# M_2_Circuit.net
KiCad netlist of a schematic drawn in Altium Designer
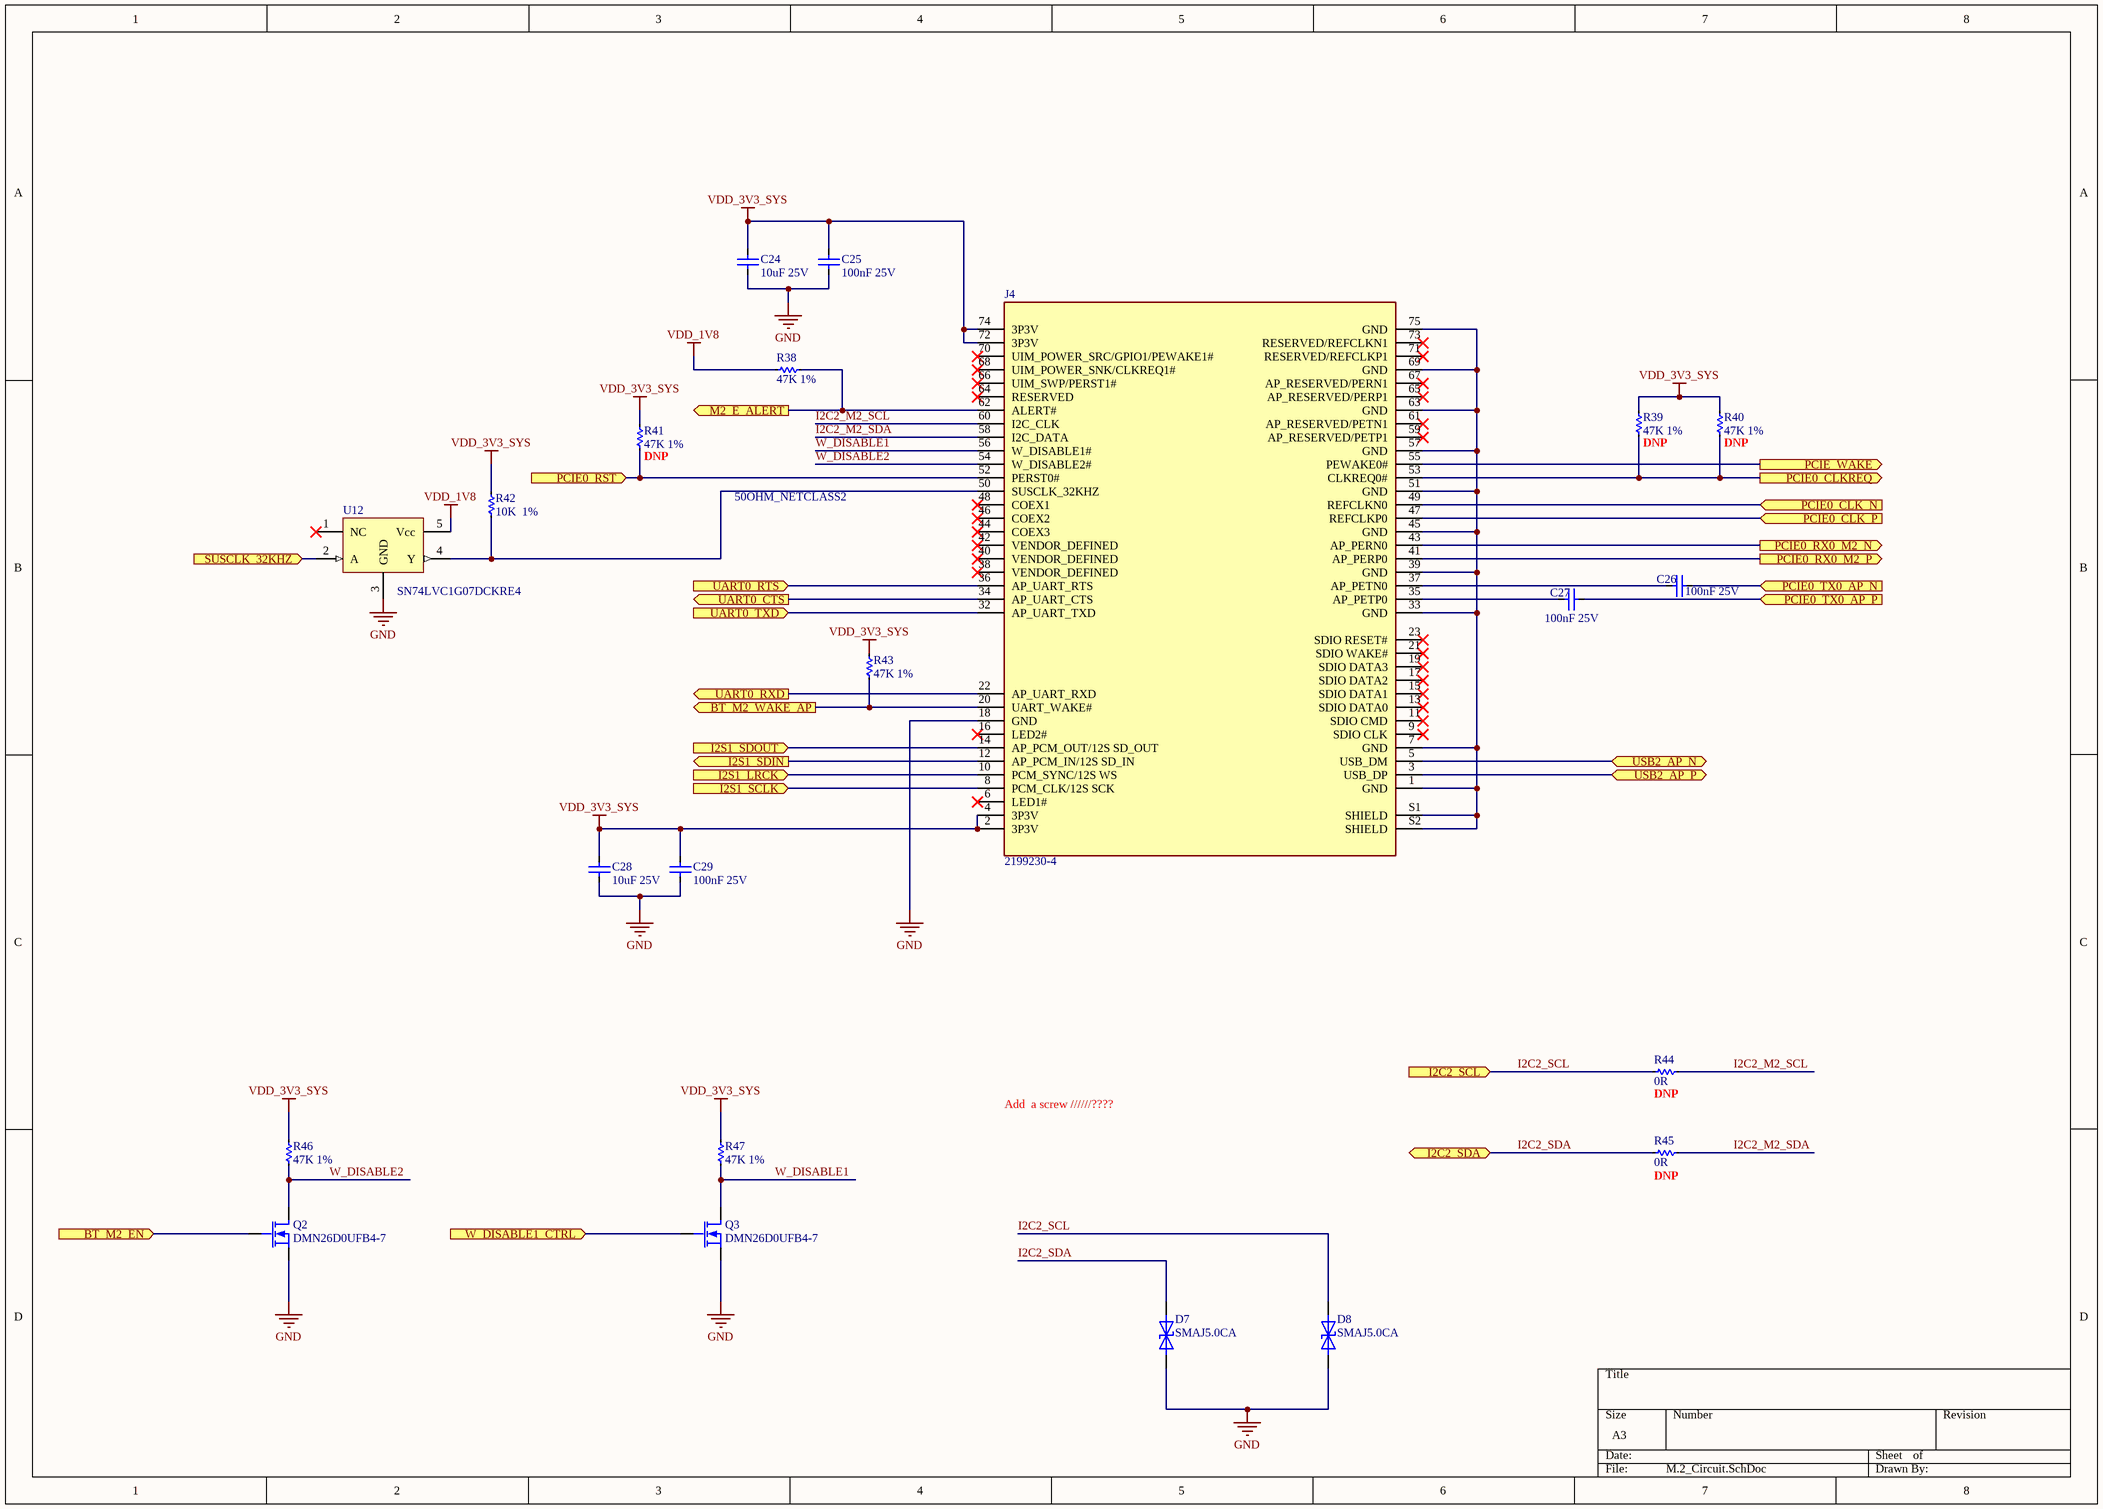
[diagram p0: M.2_Circuit.SchDoc]

(export (version "E")
  (design (tool "Eeschema 10.0.6"))
  (components
    (comp (ref "C24")
      (value "10uF 25V")
      (footprint "C0805")
      (description "Ceramic capacitor SMD-0805 10000nF (10uF) /25V X5R# M +-20% Samsung , RoHS/3000pcs/")
      (fields
        (field (name "MANUFACTURER") "Samsung")
        (field (name "MANUFACTURER PART NUMBER") "CL21A106KAYNNNG")
      )
      (libsource (lib "GM_Altium_Library") (part "CL21A106KAYNNNG"))
    )
    (comp (ref "C25")
      (value "100nF 25V")
      (footprint "C0402")
      (description "CAP CER 0.1UF 25V X5R 0402 / High Value Multilayer Ceramic Capacitors (High dielectric type)")
      (fields
        (field (name "MANUFACTURER") "Taiyo Yuden")
        (field (name "MANUFACTURER PART NUMBER") "TMK105BJ104KV-F")
      )
      (libsource (lib "GM_Altium_Library") (part "TMK105BJ104KV-F"))
    )
    (comp (ref "C26")
      (value "100nF 25V")
      (footprint "C0402")
      (description "CAP CER 0.1UF 25V X5R 0402 / High Value Multilayer Ceramic Capacitors (High dielectric type)")
      (fields
        (field (name "MANUFACTURER") "Taiyo Yuden")
        (field (name "MANUFACTURER PART NUMBER") "TMK105BJ104KV-F")
      )
      (libsource (lib "GM_Altium_Library") (part "TMK105BJ104KV-F"))
    )
    (comp (ref "C27")
      (value "100nF 25V")
      (footprint "C0402")
      (description "CAP CER 0.1UF 25V X5R 0402 / High Value Multilayer Ceramic Capacitors (High dielectric type)")
      (fields
        (field (name "MANUFACTURER") "Taiyo Yuden")
        (field (name "MANUFACTURER PART NUMBER") "TMK105BJ104KV-F")
      )
      (libsource (lib "GM_Altium_Library") (part "TMK105BJ104KV-F"))
    )
    (comp (ref "C28")
      (value "10uF 25V")
      (footprint "C0805")
      (description "Ceramic capacitor SMD-0805 10000nF (10uF) /25V X5R# M +-20% Samsung , RoHS/3000pcs/")
      (fields
        (field (name "MANUFACTURER") "Samsung")
        (field (name "MANUFACTURER PART NUMBER") "CL21A106KAYNNNG")
      )
      (libsource (lib "GM_Altium_Library") (part "CL21A106KAYNNNG"))
    )
    (comp (ref "C29")
      (value "100nF 25V")
      (footprint "C0402")
      (description "CAP CER 0.1UF 25V X5R 0402 / High Value Multilayer Ceramic Capacitors (High dielectric type)")
      (fields
        (field (name "MANUFACTURER") "Taiyo Yuden")
        (field (name "MANUFACTURER PART NUMBER") "TMK105BJ104KV-F")
      )
      (libsource (lib "GM_Altium_Library") (part "TMK105BJ104KV-F"))
    )
    (comp (ref "D7")
      (value "SMAJ5.0CA")
      (footprint "DO-214AC")
      (fields (field (name "MANUFACTURER") "Littelfuse"))
      (libsource (lib "GM_Altium_Library") (part "SMAJ5.0CA"))
    )
    (comp (ref "D8")
      (value "SMAJ5.0CA")
      (footprint "DO-214AC")
      (fields (field (name "MANUFACTURER") "Littelfuse"))
      (libsource (lib "GM_Altium_Library") (part "SMAJ5.0CA"))
    )
    (comp (ref "J4")
      (value "2199230-4")
      (footprint "2199230-4")
      (description "Conn Card Edge SKT 67 POS 0.5mm Solder RA SMD T/R")
      (fields (field (name "MANUFACTURER") "TE Connectivity"))
      (libsource (lib "GM_Connector") (part "2199230-4"))
    )
    (comp (ref "Q2")
      (value "DMN26D0UFB4-7")
      (footprint "DFN1006-3")
      (description "Single N-Channel 20 V 350 mW Silicon Surface Mount Mosfet - DFN-3")
      (fields (field (name "MANUFACTURER") "Diodes"))
      (libsource (lib "GM_Altium_Library") (part "DMN26D0UFB4-7"))
    )
    (comp (ref "Q3")
      (value "DMN26D0UFB4-7")
      (footprint "DFN1006-3")
      (description "Single N-Channel 20 V 350 mW Silicon Surface Mount Mosfet - DFN-3")
      (fields (field (name "MANUFACTURER") "Diodes"))
      (libsource (lib "GM_Altium_Library") (part "DMN26D0UFB4-7"))
    )
    (comp (ref "R38")
      (value "47K 1%")
      (footprint "R0402")
      (description "Res General Purpose Thick Film 0402 47K Ohm 1% 1/16W ±100ppm/°C Molded SMD Paper T/R")
      (fields
        (field (name "MANUFACTURER") "Yageo")
        (field (name "MANUFACTURER PART NUMBER") "RC0402FR-0747KL")
      )
      (libsource (lib "GM_Altium_Library") (part "RC0402FR-0747KL"))
    )
    (comp (ref "R39")
      (value "47K 1%")
      (footprint "R0402")
      (description "Res General Purpose Thick Film 0402 47K Ohm 1% 1/16W ±100ppm/°C Molded SMD Paper T/R")
      (fields
        (field (name "MANUFACTURER") "Yageo")
        (field (name "MANUFACTURER PART NUMBER") "RC0402FR-0747KL")
      )
      (libsource (lib "GM_Altium_Library") (part "RC0402FR-0747KL"))
    )
    (comp (ref "R40")
      (value "47K 1%")
      (footprint "R0402")
      (description "Res General Purpose Thick Film 0402 47K Ohm 1% 1/16W ±100ppm/°C Molded SMD Paper T/R")
      (fields
        (field (name "MANUFACTURER") "Yageo")
        (field (name "MANUFACTURER PART NUMBER") "RC0402FR-0747KL")
      )
      (libsource (lib "GM_Altium_Library") (part "RC0402FR-0747KL"))
    )
    (comp (ref "R41")
      (value "47K 1%")
      (footprint "R0402")
      (description "Res General Purpose Thick Film 0402 47K Ohm 1% 1/16W ±100ppm/°C Molded SMD Paper T/R")
      (fields
        (field (name "MANUFACTURER") "Yageo")
        (field (name "MANUFACTURER PART NUMBER") "RC0402FR-0747KL")
      )
      (libsource (lib "GM_Altium_Library") (part "RC0402FR-0747KL"))
    )
    (comp (ref "R42")
      (value "10K  1%")
      (footprint "R0402")
      (description "Res General Purpose Thick Film 0402 10K Ohm 1% 1/16W ±100ppm/°C Molded SMD Paper T/R")
      (fields
        (field (name "MANUFACTURER") "Yageo")
        (field (name "MANUFACTURER PART NUMBER") "RC0402FR-0710KP")
      )
      (libsource (lib "GM_Altium_Library") (part "RC0402FR-0710KP"))
    )
    (comp (ref "R43")
      (value "47K 1%")
      (footprint "R0402")
      (description "Res General Purpose Thick Film 0402 47K Ohm 1% 1/16W ±100ppm/°C Molded SMD Paper T/R")
      (fields
        (field (name "MANUFACTURER") "Yageo")
        (field (name "MANUFACTURER PART NUMBER") "RC0402FR-0747KL")
      )
      (libsource (lib "GM_Altium_Library") (part "RC0402FR-0747KL"))
    )
    (comp (ref "R44")
      (value "0R")
      (footprint "R0603")
      (description "RES SMD 0 OHM JUMPER 1/10W 0603")
      (fields
        (field (name "MANUFACTURER") "Bourns")
        (field (name "MANUFACTURER PART NUMBER") "CR0603-J/-000ELF")
      )
      (libsource (lib "GM_Altium_Library") (part "CR0603-J/-000ELF"))
    )
    (comp (ref "R45")
      (value "0R")
      (footprint "R0603")
      (description "RES SMD 0 OHM JUMPER 1/10W 0603")
      (fields
        (field (name "MANUFACTURER") "Bourns")
        (field (name "MANUFACTURER PART NUMBER") "CR0603-J/-000ELF")
      )
      (libsource (lib "GM_Altium_Library") (part "CR0603-J/-000ELF"))
    )
    (comp (ref "R46")
      (value "47K 1%")
      (footprint "R0402")
      (description "Res General Purpose Thick Film 0402 47K Ohm 1% 1/16W ±100ppm/°C Molded SMD Paper T/R")
      (fields
        (field (name "MANUFACTURER") "Yageo")
        (field (name "MANUFACTURER PART NUMBER") "RC0402FR-0747KL")
      )
      (libsource (lib "GM_Altium_Library") (part "RC0402FR-0747KL"))
    )
    (comp (ref "R47")
      (value "47K 1%")
      (footprint "R0402")
      (description "Res General Purpose Thick Film 0402 47K Ohm 1% 1/16W ±100ppm/°C Molded SMD Paper T/R")
      (fields
        (field (name "MANUFACTURER") "Yageo")
        (field (name "MANUFACTURER PART NUMBER") "RC0402FR-0747KL")
      )
      (libsource (lib "GM_Altium_Library") (part "RC0402FR-0747KL"))
    )
    (comp (ref "U12")
      (value "SN74LVC1G07DCKRE4")
      (footprint "SC70-5")
      (description "Single 1.65-V to 5.5-V buffer with open-drain outputs 5-SC70 -40 to 125")
      (fields (field (name "MANUFACTURER") "Texas Instruments"))
      (libsource (lib "GM_Altium_Library") (part "SN74LVC1G07DCKRE4"))
    )
  )
  (nets
    (net (code "1") (name "/BT_M2_EN") (class "Default")
      (node (ref "Q2") (pin "1") (pinfunction "G_1") (pintype "passive"))
    )
    (net (code "2") (name "/BT_M2_WAKE_AP") (class "Default")
      (node (ref "J4") (pin "20") (pinfunction "UART_WAKE#_20") (pintype "passive"))
      (node (ref "R43") (pin "1") (pinfunction "1_1") (pintype "passive"))
    )
    (net (code "3") (name "/I2C2_M2_SCL") (class "Default")
      (node (ref "J4") (pin "60") (pinfunction "I2C_CLK_60") (pintype "passive"))
      (node (ref "R44") (pin "1") (pinfunction "1_1") (pintype "passive"))
    )
    (net (code "4") (name "/I2C2_M2_SDA") (class "Default")
      (node (ref "J4") (pin "58") (pinfunction "I2C_DATA_58") (pintype "passive"))
      (node (ref "R45") (pin "1") (pinfunction "1_1") (pintype "passive"))
    )
    (net (code "5") (name "/I2C2_SCL") (class "Default")
      (node (ref "D8") (pin "A") (pinfunction "A_A") (pintype "passive"))
      (node (ref "R44") (pin "2") (pinfunction "2_2") (pintype "passive"))
    )
    (net (code "6") (name "/I2C2_SDA") (class "Default")
      (node (ref "D7") (pin "A") (pinfunction "A_A") (pintype "passive"))
      (node (ref "R45") (pin "2") (pinfunction "2_2") (pintype "passive"))
    )
    (net (code "7") (name "/I2S1_LRCK") (class "Default")
      (node (ref "J4") (pin "10") (pinfunction "PCM_SYNC/12S_WS_10") (pintype "passive"))
    )
    (net (code "8") (name "/I2S1_SCLK") (class "Default")
      (node (ref "J4") (pin "8") (pinfunction "PCM_CLK/12S_SCK_8") (pintype "passive"))
    )
    (net (code "9") (name "/I2S1_SDIN") (class "Default")
      (node (ref "J4") (pin "12") (pinfunction "AP_PCM_IN/12S_SD_IN_12") (pintype "passive"))
    )
    (net (code "10") (name "/I2S1_SDOUT") (class "Default")
      (node (ref "J4") (pin "14") (pinfunction "AP_PCM_OUT/12S_SD_OUT_14") (pintype "passive"))
    )
    (net (code "11") (name "/M2_E_ALERT") (class "Default")
      (node (ref "J4") (pin "62") (pinfunction "ALERT#_62") (pintype "passive"))
      (node (ref "R38") (pin "2") (pinfunction "2_2") (pintype "passive"))
    )
    (net (code "12") (name "/PCIE0_CLKREQ") (class "Default")
      (node (ref "J4") (pin "53") (pinfunction "CLKREQ0#_53") (pintype "passive"))
      (node (ref "R39") (pin "1") (pinfunction "1_1") (pintype "passive"))
      (node (ref "R40") (pin "1") (pinfunction "1_1") (pintype "passive"))
    )
    (net (code "13") (name "/PCIE0_CLK_N") (class "Default")
      (node (ref "J4") (pin "49") (pinfunction "REFCLKN0_49") (pintype "passive"))
    )
    (net (code "14") (name "/PCIE0_CLK_P") (class "Default")
      (node (ref "J4") (pin "47") (pinfunction "REFCLKP0_47") (pintype "passive"))
    )
    (net (code "15") (name "/PCIE0_RST") (class "Default")
      (node (ref "J4") (pin "52") (pinfunction "PERST0#_52") (pintype "passive"))
      (node (ref "R41") (pin "1") (pinfunction "1_1") (pintype "passive"))
    )
    (net (code "16") (name "/PCIE0_RX0_M2_N") (class "Default")
      (node (ref "J4") (pin "43") (pinfunction "AP_PERN0_43") (pintype "passive"))
    )
    (net (code "17") (name "/PCIE0_RX0_M2_P") (class "Default")
      (node (ref "J4") (pin "41") (pinfunction "AP_PERP0_41") (pintype "passive"))
    )
    (net (code "18") (name "/PCIE0_TX0_AP_N") (class "Default")
      (node (ref "C26") (pin "1") (pinfunction "1_1") (pintype "passive"))
    )
    (net (code "19") (name "/PCIE0_TX0_AP_P") (class "Default")
      (node (ref "C27") (pin "1") (pinfunction "1_1") (pintype "passive"))
    )
    (net (code "20") (name "/PCIE_WAKE") (class "Default")
      (node (ref "J4") (pin "55") (pinfunction "PEWAKE0#_55") (pintype "passive"))
    )
    (net (code "21") (name "/SUSCLK_32KHZ") (class "Default")
      (node (ref "U12") (pin "2") (pinfunction "A_2") (pintype "input"))
    )
    (net (code "22") (name "/UART0_CTS") (class "Default")
      (node (ref "J4") (pin "34") (pinfunction "AP_UART_CTS_34") (pintype "passive"))
    )
    (net (code "23") (name "/UART0_RTS") (class "Default")
      (node (ref "J4") (pin "36") (pinfunction "AP_UART_RTS_36") (pintype "passive"))
    )
    (net (code "24") (name "/UART0_RXD") (class "Default")
      (node (ref "J4") (pin "22") (pinfunction "AP_UART_RXD_22") (pintype "passive"))
    )
    (net (code "25") (name "/UART0_TXD") (class "Default")
      (node (ref "J4") (pin "32") (pinfunction "AP_UART_TXD_32") (pintype "passive"))
    )
    (net (code "26") (name "/USB2_AP_N") (class "Default")
      (node (ref "J4") (pin "5") (pinfunction "USB_DM_5") (pintype "passive"))
    )
    (net (code "27") (name "/USB2_AP_P") (class "Default")
      (node (ref "J4") (pin "3") (pinfunction "USB_DP_3") (pintype "passive"))
    )
    (net (code "28") (name "/W_DISABLE1") (class "Default")
      (node (ref "J4") (pin "56") (pinfunction "W_DISABLE1#_56") (pintype "passive"))
      (node (ref "Q3") (pin "3") (pinfunction "D_3") (pintype "passive"))
      (node (ref "R47") (pin "1") (pinfunction "1_1") (pintype "passive"))
    )
    (net (code "29") (name "/W_DISABLE1_CTRL") (class "Default")
      (node (ref "Q3") (pin "1") (pinfunction "G_1") (pintype "passive"))
    )
    (net (code "30") (name "/W_DISABLE2") (class "Default")
      (node (ref "J4") (pin "54") (pinfunction "W_DISABLE2#_54") (pintype "passive"))
      (node (ref "Q2") (pin "3") (pinfunction "D_3") (pintype "passive"))
      (node (ref "R46") (pin "1") (pinfunction "1_1") (pintype "passive"))
    )
    (net (code "31") (name "GND") (class "Default")
      (node (ref "C24") (pin "1") (pinfunction "1_1") (pintype "passive"))
      (node (ref "C25") (pin "1") (pinfunction "1_1") (pintype "passive"))
      (node (ref "C28") (pin "1") (pinfunction "1_1") (pintype "passive"))
      (node (ref "C29") (pin "1") (pinfunction "1_1") (pintype "passive"))
      (node (ref "D7") (pin "C") (pinfunction "C_C") (pintype "passive"))
      (node (ref "D8") (pin "C") (pinfunction "C_C") (pintype "passive"))
      (node (ref "J4") (pin "18") (pinfunction "GND_18") (pintype "passive"))
      (node (ref "Q2") (pin "2") (pinfunction "S_2") (pintype "passive"))
      (node (ref "Q3") (pin "2") (pinfunction "S_2") (pintype "passive"))
      (node (ref "U12") (pin "3") (pinfunction "GND_3") (pintype "power_in"))
    )
    (net (code "32") (name "Net-(J4-AP_PETN0)") (class "Default")
      (node (ref "C26") (pin "2") (pinfunction "2_2") (pintype "passive"))
      (node (ref "J4") (pin "37") (pinfunction "AP_PETN0_37") (pintype "passive"))
    )
    (net (code "33") (name "Net-(J4-AP_PETP0)") (class "Default")
      (node (ref "C27") (pin "2") (pinfunction "2_2") (pintype "passive"))
      (node (ref "J4") (pin "35") (pinfunction "AP_PETP0_35") (pintype "passive"))
    )
    (net (code "34") (name "Net-(J4-GND-Pad1)") (class "Default")
      (node (ref "J4") (pin "1") (pinfunction "GND_1") (pintype "passive"))
      (node (ref "J4") (pin "33") (pinfunction "GND_33") (pintype "passive"))
      (node (ref "J4") (pin "39") (pinfunction "GND_39") (pintype "passive"))
      (node (ref "J4") (pin "45") (pinfunction "GND_45") (pintype "passive"))
      (node (ref "J4") (pin "51") (pinfunction "GND_51") (pintype "passive"))
      (node (ref "J4") (pin "57") (pinfunction "GND_57") (pintype "passive"))
      (node (ref "J4") (pin "63") (pinfunction "GND_63") (pintype "passive"))
      (node (ref "J4") (pin "69") (pinfunction "GND_69") (pintype "passive"))
      (node (ref "J4") (pin "7") (pinfunction "GND_7") (pintype "passive"))
      (node (ref "J4") (pin "75") (pinfunction "GND_75") (pintype "passive"))
      (node (ref "J4") (pin "S1") (pinfunction "SHIELD_S1") (pintype "passive"))
      (node (ref "J4") (pin "S2") (pinfunction "SHIELD_S2") (pintype "passive"))
    )
    (net (code "35") (name "Net-(J4-SUSCLK_32KHZ)") (class "Default")
      (node (ref "J4") (pin "50") (pinfunction "SUSCLK_32KHZ_50") (pintype "passive"))
      (node (ref "R42") (pin "1") (pinfunction "1_1") (pintype "passive"))
      (node (ref "U12") (pin "4") (pinfunction "Y_4") (pintype "output"))
    )
    (net (code "36") (name "VDD_1V8") (class "Default")
      (node (ref "R38") (pin "1") (pinfunction "1_1") (pintype "passive"))
      (node (ref "U12") (pin "5") (pinfunction "Vcc_5") (pintype "power_in"))
    )
    (net (code "37") (name "VDD_3V3_SYS") (class "Default")
      (node (ref "C24") (pin "2") (pinfunction "2_2") (pintype "passive"))
      (node (ref "C25") (pin "2") (pinfunction "2_2") (pintype "passive"))
      (node (ref "C28") (pin "2") (pinfunction "2_2") (pintype "passive"))
      (node (ref "C29") (pin "2") (pinfunction "2_2") (pintype "passive"))
      (node (ref "J4") (pin "2") (pinfunction "3P3V_2") (pintype "passive"))
      (node (ref "J4") (pin "4") (pinfunction "3P3V_4") (pintype "passive"))
      (node (ref "J4") (pin "72") (pinfunction "3P3V_72") (pintype "passive"))
      (node (ref "J4") (pin "74") (pinfunction "3P3V_74") (pintype "passive"))
      (node (ref "R39") (pin "2") (pinfunction "2_2") (pintype "passive"))
      (node (ref "R40") (pin "2") (pinfunction "2_2") (pintype "passive"))
      (node (ref "R41") (pin "2") (pinfunction "2_2") (pintype "passive"))
      (node (ref "R42") (pin "2") (pinfunction "2_2") (pintype "passive"))
      (node (ref "R43") (pin "2") (pinfunction "2_2") (pintype "passive"))
      (node (ref "R46") (pin "2") (pinfunction "2_2") (pintype "passive"))
      (node (ref "R47") (pin "2") (pinfunction "2_2") (pintype "passive"))
    )
    (net (code "38") (name "unconnected-(J4-AP_RESERVED{slash}PERN1-Pad67)") (class "Default")
      (node (ref "J4") (pin "67") (pinfunction "AP_RESERVED/PERN1_67") (pintype "passive+no_connect"))
    )
    (net (code "39") (name "unconnected-(J4-AP_RESERVED{slash}PERP1-Pad65)") (class "Default")
      (node (ref "J4") (pin "65") (pinfunction "AP_RESERVED/PERP1_65") (pintype "passive+no_connect"))
    )
    (net (code "40") (name "unconnected-(J4-AP_RESERVED{slash}PETN1-Pad61)") (class "Default")
      (node (ref "J4") (pin "61") (pinfunction "AP_RESERVED/PETN1_61") (pintype "passive+no_connect"))
    )
    (net (code "41") (name "unconnected-(J4-AP_RESERVED{slash}PETP1-Pad59)") (class "Default")
      (node (ref "J4") (pin "59") (pinfunction "AP_RESERVED/PETP1_59") (pintype "passive+no_connect"))
    )
    (net (code "42") (name "unconnected-(J4-COEX1-Pad48)") (class "Default")
      (node (ref "J4") (pin "48") (pinfunction "COEX1_48") (pintype "passive+no_connect"))
    )
    (net (code "43") (name "unconnected-(J4-COEX2-Pad46)") (class "Default")
      (node (ref "J4") (pin "46") (pinfunction "COEX2_46") (pintype "passive+no_connect"))
    )
    (net (code "44") (name "unconnected-(J4-COEX3-Pad44)") (class "Default")
      (node (ref "J4") (pin "44") (pinfunction "COEX3_44") (pintype "passive+no_connect"))
    )
    (net (code "45") (name "unconnected-(J4-LED1#-Pad6)") (class "Default")
      (node (ref "J4") (pin "6") (pinfunction "LED1#_6") (pintype "passive+no_connect"))
    )
    (net (code "46") (name "unconnected-(J4-LED2#-Pad16)") (class "Default")
      (node (ref "J4") (pin "16") (pinfunction "LED2#_16") (pintype "passive+no_connect"))
    )
    (net (code "47") (name "unconnected-(J4-RESERVED-Pad64)") (class "Default")
      (node (ref "J4") (pin "64") (pinfunction "RESERVED_64") (pintype "passive+no_connect"))
    )
    (net (code "48") (name "unconnected-(J4-RESERVED{slash}REFCLKN1-Pad73)") (class "Default")
      (node (ref "J4") (pin "73") (pinfunction "RESERVED/REFCLKN1_73") (pintype "passive+no_connect"))
    )
    (net (code "49") (name "unconnected-(J4-RESERVED{slash}REFCLKP1-Pad71)") (class "Default")
      (node (ref "J4") (pin "71") (pinfunction "RESERVED/REFCLKP1_71") (pintype "passive+no_connect"))
    )
    (net (code "50") (name "unconnected-(J4-SDIO_CLK-Pad9)") (class "Default")
      (node (ref "J4") (pin "9") (pinfunction "SDIO_CLK_9") (pintype "passive+no_connect"))
    )
    (net (code "51") (name "unconnected-(J4-SDIO_CMD-Pad11)") (class "Default")
      (node (ref "J4") (pin "11") (pinfunction "SDIO_CMD_11") (pintype "passive+no_connect"))
    )
    (net (code "52") (name "unconnected-(J4-SDIO_DATA0-Pad13)") (class "Default")
      (node (ref "J4") (pin "13") (pinfunction "SDIO_DATA0_13") (pintype "passive+no_connect"))
    )
    (net (code "53") (name "unconnected-(J4-SDIO_DATA1-Pad15)") (class "Default")
      (node (ref "J4") (pin "15") (pinfunction "SDIO_DATA1_15") (pintype "passive+no_connect"))
    )
    (net (code "54") (name "unconnected-(J4-SDIO_DATA2-Pad17)") (class "Default")
      (node (ref "J4") (pin "17") (pinfunction "SDIO_DATA2_17") (pintype "passive+no_connect"))
    )
    (net (code "55") (name "unconnected-(J4-SDIO_DATA3-Pad19)") (class "Default")
      (node (ref "J4") (pin "19") (pinfunction "SDIO_DATA3_19") (pintype "passive+no_connect"))
    )
    (net (code "56") (name "unconnected-(J4-SDIO_RESET#-Pad23)") (class "Default")
      (node (ref "J4") (pin "23") (pinfunction "SDIO_RESET#_23") (pintype "passive+no_connect"))
    )
    (net (code "57") (name "unconnected-(J4-SDIO_WAKE#-Pad21)") (class "Default")
      (node (ref "J4") (pin "21") (pinfunction "SDIO_WAKE#_21") (pintype "passive+no_connect"))
    )
    (net (code "58") (name "unconnected-(J4-UIM_POWER_SNK{slash}CLKREQ1#-Pad68)") (class "Default")
      (node (ref "J4") (pin "68") (pinfunction "UIM_POWER_SNK/CLKREQ1#_68") (pintype "passive+no_connect"))
    )
    (net (code "59") (name "unconnected-(J4-UIM_POWER_SRC{slash}GPIO1{slash}PEWAKE1#-Pad70)") (class "Default")
      (node (ref "J4") (pin "70") (pinfunction "UIM_POWER_SRC/GPIO1/PEWAKE1#_70") (pintype "passive+no_connect"))
    )
    (net (code "60") (name "unconnected-(J4-UIM_SWP{slash}PERST1#-Pad66)") (class "Default")
      (node (ref "J4") (pin "66") (pinfunction "UIM_SWP/PERST1#_66") (pintype "passive+no_connect"))
    )
    (net (code "61") (name "unconnected-(J4-VENDOR_DEFINED-Pad38)") (class "Default")
      (node (ref "J4") (pin "38") (pinfunction "VENDOR_DEFINED_38") (pintype "passive+no_connect"))
    )
    (net (code "62") (name "unconnected-(J4-VENDOR_DEFINED-Pad40)") (class "Default")
      (node (ref "J4") (pin "40") (pinfunction "VENDOR_DEFINED_40") (pintype "passive+no_connect"))
    )
    (net (code "63") (name "unconnected-(J4-VENDOR_DEFINED-Pad42)") (class "Default")
      (node (ref "J4") (pin "42") (pinfunction "VENDOR_DEFINED_42") (pintype "passive+no_connect"))
    )
    (net (code "64") (name "unconnected-(U12-NC-Pad1)") (class "Default")
      (node (ref "U12") (pin "1") (pinfunction "NC_1") (pintype "passive+no_connect"))
    )
  )
)
